# NRF.net
KiCad netlist of a schematic drawn in Altium Designer
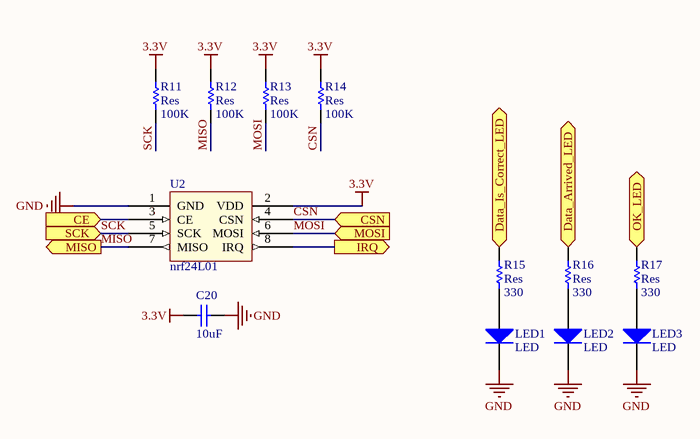
[diagram p0: NRF.SchDoc]

(export (version "E")
  (design (tool "Eeschema 10.0.6"))
  (components
    (comp (ref "C20")
      (value "10uF")
      (footprint "2012[0805]")
      (description "Capacitor")
      (fields (field (name "Comment") "Cap_UP") (field (name "PUBLISHER") "Altium Limited"))
      (libsource (lib "KN2CLib") (part "Cap_UP"))
    )
    (comp (ref "LED1")
      (value "LED")
      (footprint "2012[0805]")
      (description "1 Amp General Purpose Rectifier")
      (fields (field (name "PUBLISHER") "Altium Limited"))
      (libsource (lib "KN2CLib") (part "Diode"))
    )
    (comp (ref "LED2")
      (value "LED")
      (footprint "2012[0805]")
      (description "1 Amp General Purpose Rectifier")
      (fields (field (name "PUBLISHER") "Altium Limited"))
      (libsource (lib "KN2CLib") (part "Diode"))
    )
    (comp (ref "LED3")
      (value "LED")
      (footprint "2012[0805]")
      (description "1 Amp General Purpose Rectifier")
      (fields (field (name "PUBLISHER") "Altium Limited"))
      (libsource (lib "KN2CLib") (part "Diode"))
    )
    (comp (ref "R11")
      (value "Res")
      (footprint "2012[0805]")
      (description "Semiconductor Resistor")
      (fields (field (name "ALTIUM_VALUE") "100K") (field (name "PUBLISHER") "Altium Limited"))
      (libsource (lib "KN2CLib") (part "Res"))
    )
    (comp (ref "R12")
      (value "Res")
      (footprint "2012[0805]")
      (description "Semiconductor Resistor")
      (fields (field (name "ALTIUM_VALUE") "100K") (field (name "PUBLISHER") "Altium Limited"))
      (libsource (lib "KN2CLib") (part "Res"))
    )
    (comp (ref "R13")
      (value "Res")
      (footprint "2012[0805]")
      (description "Semiconductor Resistor")
      (fields (field (name "ALTIUM_VALUE") "100K") (field (name "PUBLISHER") "Altium Limited"))
      (libsource (lib "KN2CLib") (part "Res"))
    )
    (comp (ref "R14")
      (value "Res")
      (footprint "2012[0805]")
      (description "Semiconductor Resistor")
      (fields (field (name "ALTIUM_VALUE") "100K") (field (name "PUBLISHER") "Altium Limited"))
      (libsource (lib "KN2CLib") (part "Res"))
    )
    (comp (ref "R15")
      (value "Res")
      (footprint "2012[0805]")
      (description "Semiconductor Resistor")
      (fields (field (name "ALTIUM_VALUE") "330") (field (name "PUBLISHER") "Altium Limited"))
      (libsource (lib "KN2CLib") (part "Res"))
    )
    (comp (ref "R16")
      (value "Res")
      (footprint "2012[0805]")
      (description "Semiconductor Resistor")
      (fields (field (name "ALTIUM_VALUE") "330") (field (name "PUBLISHER") "Altium Limited"))
      (libsource (lib "KN2CLib") (part "Res"))
    )
    (comp (ref "R17")
      (value "Res")
      (footprint "2012[0805]")
      (description "Semiconductor Resistor")
      (fields (field (name "ALTIUM_VALUE") "330") (field (name "PUBLISHER") "Altium Limited"))
      (libsource (lib "KN2CLib") (part "Res"))
    )
    (comp (ref "U2") (value "nrf24L01") (footprint "NRF24L01") (libsource (lib "KN2CLib") (part "nrf24L01")))
  )
  (nets
    (net (code "1") (name "/CE") (class "Default")
      (node (ref "U2") (pin "3") (pinfunction "CE_3") (pintype "input"))
    )
    (net (code "2") (name "/CSN") (class "Default")
      (node (ref "R14") (pin "1") (pinfunction "1_1") (pintype "passive"))
      (node (ref "U2") (pin "4") (pinfunction "CSN_4") (pintype "input"))
    )
    (net (code "3") (name "/Data_Arrived_LED") (class "Default")
      (node (ref "R16") (pin "1") (pinfunction "1_1") (pintype "passive"))
    )
    (net (code "4") (name "/Data_Is_Correct_LED") (class "Default")
      (node (ref "R15") (pin "1") (pinfunction "1_1") (pintype "passive"))
    )
    (net (code "5") (name "/IRQ") (class "Default")
      (node (ref "U2") (pin "8") (pinfunction "IRQ_8") (pintype "output"))
    )
    (net (code "6") (name "/MISO") (class "Default")
      (node (ref "R12") (pin "1") (pinfunction "1_1") (pintype "passive"))
      (node (ref "U2") (pin "7") (pinfunction "MISO_7") (pintype "output"))
    )
    (net (code "7") (name "/MOSI") (class "Default")
      (node (ref "R13") (pin "1") (pinfunction "1_1") (pintype "passive"))
      (node (ref "U2") (pin "6") (pinfunction "MOSI_6") (pintype "input"))
    )
    (net (code "8") (name "/OK_LED") (class "Default")
      (node (ref "R17") (pin "1") (pinfunction "1_1") (pintype "passive"))
    )
    (net (code "9") (name "/SCK") (class "Default")
      (node (ref "R11") (pin "1") (pinfunction "1_1") (pintype "passive"))
      (node (ref "U2") (pin "5") (pinfunction "SCK_5") (pintype "input"))
    )
    (net (code "10") (name "3.3V") (class "Default")
      (node (ref "C20") (pin "2") (pinfunction "2_2") (pintype "passive"))
      (node (ref "R11") (pin "2") (pinfunction "2_2") (pintype "passive"))
      (node (ref "R12") (pin "2") (pinfunction "2_2") (pintype "passive"))
      (node (ref "R13") (pin "2") (pinfunction "2_2") (pintype "passive"))
      (node (ref "R14") (pin "2") (pinfunction "2_2") (pintype "passive"))
      (node (ref "U2") (pin "2") (pinfunction "VDD_2") (pintype "power_in"))
    )
    (net (code "11") (name "GND") (class "Default")
      (node (ref "C20") (pin "1") (pinfunction "1_1") (pintype "passive"))
      (node (ref "LED1") (pin "2") (pinfunction "K_2") (pintype "passive"))
      (node (ref "LED2") (pin "2") (pinfunction "K_2") (pintype "passive"))
      (node (ref "LED3") (pin "2") (pinfunction "K_2") (pintype "passive"))
      (node (ref "U2") (pin "1") (pinfunction "GND_1") (pintype "power_in"))
    )
    (net (code "12") (name "Net-(LED1-A)") (class "Default")
      (node (ref "LED1") (pin "1") (pinfunction "A_1") (pintype "passive"))
      (node (ref "R15") (pin "2") (pinfunction "2_2") (pintype "passive"))
    )
    (net (code "13") (name "Net-(LED2-A)") (class "Default")
      (node (ref "LED2") (pin "1") (pinfunction "A_1") (pintype "passive"))
      (node (ref "R16") (pin "2") (pinfunction "2_2") (pintype "passive"))
    )
    (net (code "14") (name "Net-(LED3-A)") (class "Default")
      (node (ref "LED3") (pin "1") (pinfunction "A_1") (pintype "passive"))
      (node (ref "R17") (pin "2") (pinfunction "2_2") (pintype "passive"))
    )
  )
)
